# SensorHumedad.net
KiCad netlist of a schematic drawn in Altium Designer
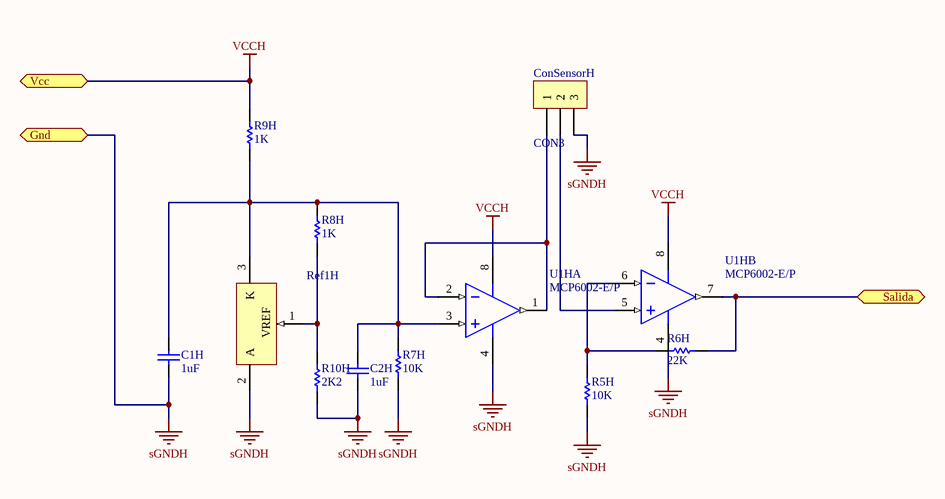
[diagram p0: SensorHumedad.SchDoc]

(export (version "E")
  (design (tool "Eeschema 10.0.6"))
  (components
    (comp (ref "C1H")
      (value "1uF")
      (footprint "CAPPOL100")
      (description "Capacitor")
      (libsource (lib "IDTILab") (part "CAP"))
    )
    (comp (ref "C2H")
      (value "1uF")
      (footprint "CAPPOL100")
      (description "Capacitor")
      (libsource (lib "IDTILab") (part "CAP"))
    )
    (comp (ref "ConSensorH")
      (value "CON3")
      (footprint "BORNERA3 - T")
      (description "Conector 3")
      (libsource (lib "IDTILab") (part "CON3"))
    )
    (comp (ref "R5H")
      (value "10K")
      (footprint "RES300")
      (description "Resistencia")
      (libsource (lib "IDTILab") (part "RES"))
    )
    (comp (ref "R6H")
      (value "22K")
      (footprint "RES300")
      (description "Resistencia")
      (libsource (lib "IDTILab") (part "RES"))
    )
    (comp (ref "R7H")
      (value "10K")
      (footprint "RES300")
      (description "Resistencia")
      (libsource (lib "IDTILab") (part "RES"))
    )
    (comp (ref "R8H")
      (value "1K")
      (footprint "RES300")
      (description "Resistencia")
      (libsource (lib "IDTILab") (part "RES"))
    )
    (comp (ref "R9H")
      (value "1K")
      (footprint "RES300")
      (description "Resistencia")
      (libsource (lib "IDTILab") (part "RES"))
    )
    (comp (ref "R10H")
      (value "2K2")
      (footprint "RES300")
      (description "Resistencia")
      (libsource (lib "IDTILab") (part "RES"))
    )
    (comp (ref "Ref1H")
      (value "TL431ACLP")
      (footprint "LP03")
      (description "Adjustable Precision Shunt Regulator")
      (fields (field (name "PUBLISHER") "Altium Limited"))
      (libsource (lib "TI Power Mgt Voltage Regulator") (part "TL431ACLP"))
    )
    (comp (ref "U1H")
      (value "MCP6002-E/P")
      (footprint "DIP8B")
      (description "1 MHz, Low-Power Operational Amplifier, 8-Pin PDIP, Extended Temperature")
      (fields (field (name "PUBLISHER") "Altium Limited"))
      (libsource (lib "Microchip Linear Devices") (part "MCP6002-E/P"))
    )
  )
  (nets
    (net (code "1") (name "/Salida") (class "Default")
      (node (ref "R6H") (pin "1") (pinfunction "1_1") (pintype "passive"))
      (node (ref "U1H") (pin "7") (pinfunction "VOUTB_7") (pintype "output"))
    )
    (net (code "2") (name "Net-(Ref1H-K)") (class "Default")
      (node (ref "C1H") (pin "2") (pinfunction "2_2") (pintype "passive"))
      (node (ref "C2H") (pin "2") (pinfunction "2_2") (pintype "passive"))
      (node (ref "R7H") (pin "2") (pinfunction "2_2") (pintype "passive"))
      (node (ref "R8H") (pin "2") (pinfunction "2_2") (pintype "passive"))
      (node (ref "R9H") (pin "1") (pinfunction "1_1") (pintype "passive"))
      (node (ref "Ref1H") (pin "3") (pinfunction "K_3") (pintype "power_in"))
      (node (ref "U1H") (pin "3") (pinfunction "VINA+_3") (pintype "input"))
    )
    (net (code "3") (name "Net-(Ref1H-VREF)") (class "Default")
      (node (ref "R10H") (pin "2") (pinfunction "2_2") (pintype "passive"))
      (node (ref "R8H") (pin "1") (pinfunction "1_1") (pintype "passive"))
      (node (ref "Ref1H") (pin "1") (pinfunction "VREF_1") (pintype "input"))
    )
    (net (code "4") (name "Net-(U1HA-VINA-)") (class "Default")
      (node (ref "ConSensorH") (pin "1") (pinfunction "1_1") (pintype "passive"))
      (node (ref "U1H") (pin "1") (pinfunction "VOUTA_1") (pintype "output"))
      (node (ref "U1H") (pin "2") (pinfunction "VINA-_2") (pintype "input"))
    )
    (net (code "5") (name "Net-(U1HB-VINB+)") (class "Default")
      (node (ref "ConSensorH") (pin "2") (pinfunction "2_2") (pintype "passive"))
      (node (ref "U1H") (pin "5") (pinfunction "VINB+_5") (pintype "input"))
    )
    (net (code "6") (name "Net-(U1HB-VINB-)") (class "Default")
      (node (ref "R5H") (pin "2") (pinfunction "2_2") (pintype "passive"))
      (node (ref "R6H") (pin "2") (pinfunction "2_2") (pintype "passive"))
      (node (ref "U1H") (pin "6") (pinfunction "VINB-_6") (pintype "input"))
    )
    (net (code "7") (name "VCCH") (class "Default")
      (node (ref "R9H") (pin "2") (pinfunction "2_2") (pintype "passive"))
      (node (ref "U1H") (pin "8") (pinfunction "VDD_8") (pintype "power_in"))
    )
    (net (code "8") (name "sGNDH") (class "Default")
      (node (ref "C1H") (pin "1") (pinfunction "1_1") (pintype "passive"))
      (node (ref "C2H") (pin "1") (pinfunction "1_1") (pintype "passive"))
      (node (ref "ConSensorH") (pin "3") (pinfunction "3_3") (pintype "passive"))
      (node (ref "R10H") (pin "1") (pinfunction "1_1") (pintype "passive"))
      (node (ref "R5H") (pin "1") (pinfunction "1_1") (pintype "passive"))
      (node (ref "R7H") (pin "1") (pinfunction "1_1") (pintype "passive"))
      (node (ref "Ref1H") (pin "2") (pinfunction "A_2") (pintype "power_in"))
      (node (ref "U1H") (pin "4") (pinfunction "VSS_4") (pintype "power_in"))
    )
  )
)
